# MCU_sheet.net
KiCad netlist of a schematic drawn in Altium Designer
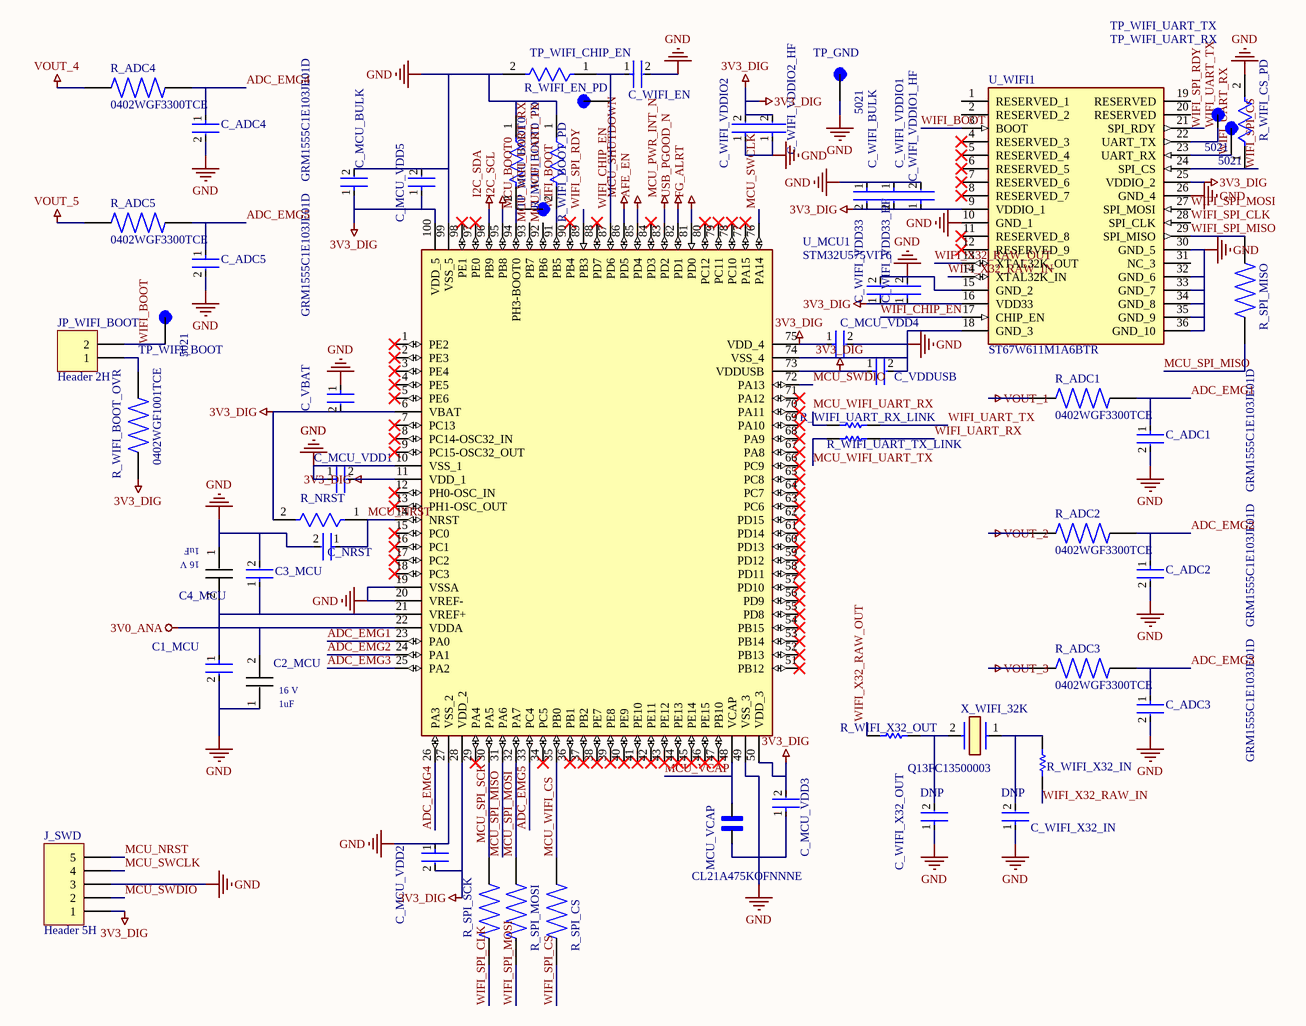
[diagram p0: MCU_sheet.SchDoc]

(export (version "E")
  (design (tool "Eeschema 10.0.6"))
  (components
    (comp (ref "C1_MCU")
      (value "GRM155R61C104KA88D")
      (footprint "96DF66F8-B997-472F-A885-42BCAAE661B2_FP-GRM155-0_05-IPC_C:FP-GRM155-0_05-IPC_C")
      (description "CAP CER 0.1UF 16V X5R 0402")
      (fields (field (name "VOLTAGE") "16V") (field (name "TOLERANCE") "10%"))
      (libsource (lib "EMG_Controlled_R5") (part "EMG_R5_C1_MCU"))
    )
    (comp (ref "C2_MCU")
      (value "MURATA_GRM155C71C105KE11D")
      (footprint "MURATA_GRM155C71C105KE11D_0:*MURATA_GRM155C71C105KE11D_0")
      (description "Murata GRM155C71C105KE11D: 1 uF 16 V X7S +/-10%, 0402/1005 metric")
      (fields (field (name "MF") "Murata") (field (name "MP") "GRM155C71C105KE11D"))
      (libsource (lib "EMG_Controlled_R5") (part "EMG_R5_C2_MCU"))
    )
    (comp (ref "C3_MCU")
      (value "GRM155R61C104KA88D")
      (footprint "96DF66F8-B997-472F-A885-42BCAAE661B2_FP-GRM155-0_05-IPC_C:FP-GRM155-0_05-IPC_C")
      (description "CAP CER 0.1UF 16V X5R 0402")
      (fields (field (name "VOLTAGE") "16V") (field (name "TOLERANCE") "10%"))
      (libsource (lib "EMG_Controlled_R5") (part "EMG_R5_C3_MCU"))
    )
    (comp (ref "C4_MCU")
      (value "MURATA_GRM155C71C105KE11D")
      (footprint "MURATA_GRM155C71C105KE11D_0:*MURATA_GRM155C71C105KE11D_0")
      (description "Murata GRM155C71C105KE11D: 1 uF 16 V X7S +/-10%, 0402/1005 metric")
      (fields (field (name "MF") "Murata") (field (name "MP") "GRM155C71C105KE11D"))
      (libsource (lib "EMG_Controlled_R5") (part "EMG_R5_C4_MCU"))
    )
    (comp (ref "C_ADC1")
      (value "GRM1555C1E103JE01D")
      (footprint "763A7EFC-D1AC-41FC-861F-90DBA274E34D_FP-GRM155-0_15-IPC_A:FP-GRM155-0_15-IPC_A")
      (description "Chip Multilayer Ceramic Capacitors for General Purpose, 0402, 10000pF, C0G, 30ppm/°C, 5%, 25V")
      (libsource (lib "EMG_Controlled_R5") (part "EMG_R5_C_ADC1"))
    )
    (comp (ref "C_ADC2")
      (value "GRM1555C1E103JE01D")
      (footprint "763A7EFC-D1AC-41FC-861F-90DBA274E34D_FP-GRM155-0_15-IPC_A:FP-GRM155-0_15-IPC_A")
      (description "Chip Multilayer Ceramic Capacitors for General Purpose, 0402, 10000pF, C0G, 30ppm/°C, 5%, 25V")
      (libsource (lib "EMG_Controlled_R5") (part "EMG_R5_C_ADC2"))
    )
    (comp (ref "C_ADC3")
      (value "GRM1555C1E103JE01D")
      (footprint "763A7EFC-D1AC-41FC-861F-90DBA274E34D_FP-GRM155-0_15-IPC_A:FP-GRM155-0_15-IPC_A")
      (description "Chip Multilayer Ceramic Capacitors for General Purpose, 0402, 10000pF, C0G, 30ppm/°C, 5%, 25V")
      (libsource (lib "EMG_Controlled_R5") (part "EMG_R5_C_ADC3"))
    )
    (comp (ref "C_ADC4")
      (value "GRM1555C1E103JE01D")
      (footprint "763A7EFC-D1AC-41FC-861F-90DBA274E34D_FP-GRM155-0_15-IPC_A:FP-GRM155-0_15-IPC_A")
      (description "Chip Multilayer Ceramic Capacitors for General Purpose, 0402, 10000pF, C0G, 30ppm/°C, 5%, 25V")
      (libsource (lib "EMG_Controlled_R5") (part "EMG_R5_C_ADC4"))
    )
    (comp (ref "C_ADC5")
      (value "GRM1555C1E103JE01D")
      (footprint "763A7EFC-D1AC-41FC-861F-90DBA274E34D_FP-GRM155-0_15-IPC_A:FP-GRM155-0_15-IPC_A")
      (description "Chip Multilayer Ceramic Capacitors for General Purpose, 0402, 10000pF, C0G, 30ppm/°C, 5%, 25V")
      (libsource (lib "EMG_Controlled_R5") (part "EMG_R5_C_ADC5"))
    )
    (comp (ref "C_MCU_BULK")
      (value "GCM21BC71E106KE36L")
      (footprint "936D640C-6583-4BC1-90EC-E059FB2B465D_FP-GCM21B-0_2-e0_2_0_7-MFG:FP-GCM21B-0_2-e0_2_0_7-MFG")
      (description "10 µF ±10% 25V Ceramic Capacitor X7S 0805 (2012 Metric)")
      (libsource (lib "EMG_Controlled_R5") (part "EMG_R5_C_MCU_BULK"))
    )
    (comp (ref "C_MCU_VDD1")
      (value "GRM155R61C104KA88D")
      (footprint "96DF66F8-B997-472F-A885-42BCAAE661B2_FP-GRM155-0_05-IPC_C:FP-GRM155-0_05-IPC_C")
      (description "CAP CER 0.1UF 16V X5R 0402")
      (fields (field (name "VOLTAGE") "16V") (field (name "TOLERANCE") "10%"))
      (libsource (lib "EMG_Controlled_R5") (part "EMG_R5_C_MCU_VDD1"))
    )
    (comp (ref "C_MCU_VDD2")
      (value "GRM155R61C104KA88D")
      (footprint "96DF66F8-B997-472F-A885-42BCAAE661B2_FP-GRM155-0_05-IPC_C:FP-GRM155-0_05-IPC_C")
      (description "CAP CER 0.1UF 16V X5R 0402")
      (fields (field (name "VOLTAGE") "16V") (field (name "TOLERANCE") "10%"))
      (libsource (lib "EMG_Controlled_R5") (part "EMG_R5_C_MCU_VDD2"))
    )
    (comp (ref "C_MCU_VDD3")
      (value "GRM155R61C104KA88D")
      (footprint "96DF66F8-B997-472F-A885-42BCAAE661B2_FP-GRM155-0_05-IPC_C:FP-GRM155-0_05-IPC_C")
      (description "CAP CER 0.1UF 16V X5R 0402")
      (fields (field (name "VOLTAGE") "16V") (field (name "TOLERANCE") "10%"))
      (libsource (lib "EMG_Controlled_R5") (part "EMG_R5_C_MCU_VDD3"))
    )
    (comp (ref "C_MCU_VDD4")
      (value "GRM155R61C104KA88D")
      (footprint "96DF66F8-B997-472F-A885-42BCAAE661B2_FP-GRM155-0_05-IPC_C:FP-GRM155-0_05-IPC_C")
      (description "CAP CER 0.1UF 16V X5R 0402")
      (fields (field (name "VOLTAGE") "16V") (field (name "TOLERANCE") "10%"))
      (libsource (lib "EMG_Controlled_R5") (part "EMG_R5_C_MCU_VDD4"))
    )
    (comp (ref "C_MCU_VDD5")
      (value "GRM155R61C104KA88D")
      (footprint "96DF66F8-B997-472F-A885-42BCAAE661B2_FP-GRM155-0_05-IPC_C:FP-GRM155-0_05-IPC_C")
      (description "CAP CER 0.1UF 16V X5R 0402")
      (fields (field (name "VOLTAGE") "16V") (field (name "TOLERANCE") "10%"))
      (libsource (lib "EMG_Controlled_R5") (part "EMG_R5_C_MCU_VDD5"))
    )
    (comp (ref "C_NRST")
      (value "GRM155R61C104KA88D")
      (footprint "96DF66F8-B997-472F-A885-42BCAAE661B2_FP-GRM155-0_05-IPC_C:FP-GRM155-0_05-IPC_C")
      (description "CAP CER 0.1UF 16V X5R 0402")
      (fields (field (name "VOLTAGE") "16V") (field (name "TOLERANCE") "10%"))
      (libsource (lib "EMG_Controlled_R5") (part "EMG_R5_C_NRST"))
    )
    (comp (ref "C_VBAT")
      (value "GRM155R61C104KA88D")
      (footprint "96DF66F8-B997-472F-A885-42BCAAE661B2_FP-GRM155-0_05-IPC_C:FP-GRM155-0_05-IPC_C")
      (description "CAP CER 0.1UF 16V X5R 0402")
      (fields (field (name "VOLTAGE") "16V") (field (name "TOLERANCE") "10%"))
      (libsource (lib "EMG_Controlled_R5") (part "EMG_R5_C_VBAT"))
    )
    (comp (ref "C_VDDUSB")
      (value "GRM155R61C104KA88D")
      (footprint "96DF66F8-B997-472F-A885-42BCAAE661B2_FP-GRM155-0_05-IPC_C:FP-GRM155-0_05-IPC_C")
      (description "CAP CER 0.1UF 16V X5R 0402")
      (fields (field (name "VOLTAGE") "16V") (field (name "TOLERANCE") "10%"))
      (libsource (lib "EMG_Controlled_R5") (part "EMG_R5_C_VDDUSB"))
    )
    (comp (ref "C_WIFI_BULK")
      (value "GRM219R60J476ME44D")
      (footprint "C53EA0CA-0507-449B-AA9E-0712004E71D5_FP-GRM219-0_2-0_1-IPC_A:FP-GRM219-0_2-0_1-IPC_A")
      (description "Chip Multilayer Ceramic Capacitors for General Purpose, 0805, 47uF, X5R, 15%, 20%, 6.3V")
      (fields (field (name "TOLERANCE") "20%"))
      (libsource (lib "EMG_Controlled_R5") (part "EMG_R5_C_WIFI_BULK"))
    )
    (comp (ref "C_WIFI_EN")
      (value "GRM155R61C104KA88D")
      (footprint "96DF66F8-B997-472F-A885-42BCAAE661B2_FP-GRM155-0_05-IPC_C:FP-GRM155-0_05-IPC_C")
      (description "CAP CER 0.1UF 16V X5R 0402")
      (fields (field (name "VOLTAGE") "16V") (field (name "TOLERANCE") "10%"))
      (libsource (lib "EMG_Controlled_R5") (part "EMG_R5_C_WIFI_EN"))
    )
    (comp (ref "C_WIFI_VDD33")
      (value "GCM21BC71E106KE36L")
      (footprint "936D640C-6583-4BC1-90EC-E059FB2B465D_FP-GCM21B-0_2-e0_2_0_7-MFG:FP-GCM21B-0_2-e0_2_0_7-MFG")
      (description "10 µF ±10% 25V Ceramic Capacitor X7S 0805 (2012 Metric)")
      (libsource (lib "EMG_Controlled_R5") (part "EMG_R5_C_WIFI_VDD33"))
    )
    (comp (ref "C_WIFI_VDD33_HF")
      (value "GRM155R61C104KA88D")
      (footprint "DB04E9CC-B2FF-43A3-BDC5-6EF387B10263_FP-GRM155-0_05-MFG:FP-GRM155-0_05-MFG")
      (description "CAP CER 0.1UF 16V X5R 0402")
      (fields (field (name "VOLTAGE") "16V") (field (name "TOLERANCE") "10%"))
      (libsource (lib "EMG_Controlled_R5") (part "EMG_R5_C_WIFI_VDD33_HF"))
    )
    (comp (ref "C_WIFI_VDDIO1")
      (value "GCM21BC71E106KE36L")
      (footprint "936D640C-6583-4BC1-90EC-E059FB2B465D_FP-GCM21B-0_2-e0_2_0_7-MFG:FP-GCM21B-0_2-e0_2_0_7-MFG")
      (description "10 µF ±10% 25V Ceramic Capacitor X7S 0805 (2012 Metric)")
      (libsource (lib "EMG_Controlled_R5") (part "EMG_R5_C_WIFI_VDDIO1"))
    )
    (comp (ref "C_WIFI_VDDIO1_HF")
      (value "GRM155R61C104KA88D")
      (footprint "DB04E9CC-B2FF-43A3-BDC5-6EF387B10263_FP-GRM155-0_05-MFG:FP-GRM155-0_05-MFG")
      (description "CAP CER 0.1UF 16V X5R 0402")
      (fields (field (name "VOLTAGE") "16V") (field (name "TOLERANCE") "10%"))
      (libsource (lib "EMG_Controlled_R5") (part "EMG_R5_C_WIFI_VDDIO1_HF"))
    )
    (comp (ref "C_WIFI_VDDIO2")
      (value "GCM21BC71E106KE36L")
      (footprint "936D640C-6583-4BC1-90EC-E059FB2B465D_FP-GCM21B-0_2-e0_2_0_7-MFG:FP-GCM21B-0_2-e0_2_0_7-MFG")
      (description "10 µF ±10% 25V Ceramic Capacitor X7S 0805 (2012 Metric)")
      (libsource (lib "EMG_Controlled_R5") (part "EMG_R5_C_WIFI_VDDIO2"))
    )
    (comp (ref "C_WIFI_VDDIO2_HF")
      (value "GRM155R61C104KA88D")
      (footprint "DB04E9CC-B2FF-43A3-BDC5-6EF387B10263_FP-GRM155-0_05-MFG:FP-GRM155-0_05-MFG")
      (description "CAP CER 0.1UF 16V X5R 0402")
      (fields (field (name "VOLTAGE") "16V") (field (name "TOLERANCE") "10%"))
      (libsource (lib "EMG_Controlled_R5") (part "EMG_R5_C_WIFI_VDDIO2_HF"))
    )
    (comp (ref "C_WIFI_X32_IN")
      (value "DNP")
      (footprint "96DF66F8-B997-472F-A885-42BCAAE661B2_FP-GRM155-0_05-IPC_C:FP-GRM155-0_05-IPC_C")
      (description "DNP - 32 kHz crystal tuning capacitor; no fitted value or MPN; retain 0402 footprint")
      (libsource (lib "EMG_Controlled_R5") (part "EMG_R5_C_WIFI_X32_IN"))
    )
    (comp (ref "C_WIFI_X32_OUT")
      (value "DNP")
      (footprint "96DF66F8-B997-472F-A885-42BCAAE661B2_FP-GRM155-0_05-IPC_C:FP-GRM155-0_05-IPC_C")
      (description "DNP - 32 kHz crystal tuning capacitor; no fitted value or MPN; retain 0402 footprint")
      (libsource (lib "EMG_Controlled_R5") (part "EMG_R5_C_WIFI_X32_OUT"))
    )
    (comp (ref "JP_WIFI_BOOT")
      (value "Header 2H")
      (footprint "EMG_Service_C2B:EMG_SJ_2P_NO")
      (description "Header, 2-Pin, Right Angle")
      (fields (field (name "PUBLISHER") "Altium Limited"))
      (libsource (lib "EMG_Controlled_R5") (part "EMG_R5_JP_WIFI_BOOT"))
    )
    (comp (ref "J_SWD")
      (value "Header 5H")
      (footprint "EMG_Service_C2B:EMG_TC2030_NL")
      (description "Header, 5-Pin, Right Angle")
      (fields (field (name "PUBLISHER") "Altium Limited"))
      (libsource (lib "EMG_Controlled_R5") (part "EMG_R5_J_SWD"))
    )
    (comp (ref "MCU_VCAP")
      (value "CL21A475KOFNNNE")
      (footprint "CL21A475KOFNNNE_0:CAPC2012X135N")
      (description "4.7 ÂµF Â±10% 16V Ceramic Capacitor X5R 0805 (2012 Metric)")
      (fields (field (name "MF") "Samsung"))
      (libsource (lib "EMG_Controlled_R5") (part "EMG_R5_MCU_VCAP"))
    )
    (comp (ref "R_ADC1")
      (value "0402WGF3300TCE")
      (footprint "0402WGF3300TCE_0:RESC1005X40N")
      (description "330 Ohm 1/16W Thick Film Resistor 0402 Chip - Surface Mount")
      (fields (field (name "MF") "Uni-Royal"))
      (libsource (lib "EMG_Controlled_R5") (part "EMG_R5_R_ADC1"))
    )
    (comp (ref "R_ADC2")
      (value "0402WGF3300TCE")
      (footprint "0402WGF3300TCE_0:RESC1005X40N")
      (description "330 Ohm 1/16W Thick Film Resistor 0402 Chip - Surface Mount")
      (fields (field (name "MF") "Uni-Royal"))
      (libsource (lib "EMG_Controlled_R5") (part "EMG_R5_R_ADC2"))
    )
    (comp (ref "R_ADC3")
      (value "0402WGF3300TCE")
      (footprint "0402WGF3300TCE_0:RESC1005X40N")
      (description "330 Ohm 1/16W Thick Film Resistor 0402 Chip - Surface Mount")
      (fields (field (name "MF") "Uni-Royal"))
      (libsource (lib "EMG_Controlled_R5") (part "EMG_R5_R_ADC3"))
    )
    (comp (ref "R_ADC4")
      (value "0402WGF3300TCE")
      (footprint "0402WGF3300TCE_0:RESC1005X40N")
      (description "330 Ohm 1/16W Thick Film Resistor 0402 Chip - Surface Mount")
      (fields (field (name "MF") "Uni-Royal"))
      (libsource (lib "EMG_Controlled_R5") (part "EMG_R5_R_ADC4"))
    )
    (comp (ref "R_ADC5")
      (value "0402WGF3300TCE")
      (footprint "0402WGF3300TCE_0:RESC1005X40N")
      (description "330 Ohm 1/16W Thick Film Resistor 0402 Chip - Surface Mount")
      (fields (field (name "MF") "Uni-Royal"))
      (libsource (lib "EMG_Controlled_R5") (part "EMG_R5_R_ADC5"))
    )
    (comp (ref "R_MCU_BOOT0_PD")
      (value "RT0402BRD0710KL")
      (footprint "B876F212-A29A-4983-9BB8-539D1BA2EBA1_FP-RT0402-MFG:FP-RT0402-MFG")
      (description "RES 10.0K OHM 1/16W .1% SMD 0402")
      (fields
        (field (name "MANUFACTURER") "Yageo")
        (field (name "OCTOPART") "https://octopart.com/rt0402brd0710kl-yageo-1181432")
      )
      (libsource (lib "EMG_Controlled_R5") (part "EMG_R5_R_MCU_BOOT0_PD"))
    )
    (comp (ref "R_NRST")
      (value "RT0402BRD0710KL")
      (footprint "B876F212-A29A-4983-9BB8-539D1BA2EBA1_FP-RT0402-MFG:FP-RT0402-MFG")
      (description "RES 10.0K OHM 1/16W .1% SMD 0402")
      (fields
        (field (name "MANUFACTURER") "Yageo")
        (field (name "OCTOPART") "https://octopart.com/rt0402brd0710kl-yageo-1181432")
      )
      (libsource (lib "EMG_Controlled_R5") (part "EMG_R5_R_NRST"))
    )
    (comp (ref "R_SPI_CS")
      (value "ERJ2RKF22R0X")
      (footprint "ERJ2RKF22R0X_0:RES_ERJ2RKF22R0X")
      (description "22 Ohms Â±1% 0.1W, 1/10W Chip Resistor 0402 (1005 Metric) Automotive AEC-Q200 Thick Film")
      (fields (field (name "MF") "Panasonic") (field (name "DIGI-KEY_PART_NUMBER") "P22.0LTR-ND"))
      (libsource (lib "EMG_Controlled_R5") (part "EMG_R5_R_SPI_CS"))
    )
    (comp (ref "R_SPI_MISO")
      (value "ERJ2RKF22R0X")
      (footprint "ERJ2RKF22R0X_0:RES_ERJ2RKF22R0X")
      (description "22 Ohms Â±1% 0.1W, 1/10W Chip Resistor 0402 (1005 Metric) Automotive AEC-Q200 Thick Film")
      (fields (field (name "MF") "Panasonic") (field (name "DIGI-KEY_PART_NUMBER") "P22.0LTR-ND"))
      (libsource (lib "EMG_Controlled_R5") (part "EMG_R5_R_SPI_MISO"))
    )
    (comp (ref "R_SPI_MOSI")
      (value "ERJ2RKF22R0X")
      (footprint "ERJ2RKF22R0X_0:RES_ERJ2RKF22R0X")
      (description "22 Ohms Â±1% 0.1W, 1/10W Chip Resistor 0402 (1005 Metric) Automotive AEC-Q200 Thick Film")
      (fields (field (name "MF") "Panasonic") (field (name "DIGI-KEY_PART_NUMBER") "P22.0LTR-ND"))
      (libsource (lib "EMG_Controlled_R5") (part "EMG_R5_R_SPI_MOSI"))
    )
    (comp (ref "R_SPI_SCK")
      (value "ERJ2RKF22R0X")
      (footprint "ERJ2RKF22R0X_0:RES_ERJ2RKF22R0X")
      (description "22 Ohms Â±1% 0.1W, 1/10W Chip Resistor 0402 (1005 Metric) Automotive AEC-Q200 Thick Film")
      (fields (field (name "MF") "Panasonic") (field (name "DIGI-KEY_PART_NUMBER") "P22.0LTR-ND"))
      (libsource (lib "EMG_Controlled_R5") (part "EMG_R5_R_SPI_SCK"))
    )
    (comp (ref "R_WIFI_BOOT_OVR")
      (value "0402WGF1001TCE")
      (footprint "0402WGF1001TCE_0:RESC1005X40N")
      (description "1K Ohm 1/16W Thick Film Resistor 0402 Chip - Surface Mount")
      (fields (field (name "MF") "Uni-Royal"))
      (libsource (lib "EMG_Controlled_R5") (part "EMG_R5_R_WIFI_BOOT_OVR"))
    )
    (comp (ref "R_WIFI_BOOT_PD")
      (value "RT0402BRD0710KL")
      (footprint "B876F212-A29A-4983-9BB8-539D1BA2EBA1_FP-RT0402-MFG:FP-RT0402-MFG")
      (description "RES 10.0K OHM 1/16W .1% SMD 0402")
      (fields
        (field (name "MANUFACTURER") "Yageo")
        (field (name "OCTOPART") "https://octopart.com/rt0402brd0710kl-yageo-1181432")
      )
      (libsource (lib "EMG_Controlled_R5") (part "EMG_R5_R_WIFI_BOOT_PD"))
    )
    (comp (ref "R_WIFI_CS_PD")
      (value "RT0402BRD0710KL")
      (footprint "B876F212-A29A-4983-9BB8-539D1BA2EBA1_FP-RT0402-MFG:FP-RT0402-MFG")
      (description "RES 10.0K OHM 1/16W .1% SMD 0402")
      (fields
        (field (name "MANUFACTURER") "Yageo")
        (field (name "OCTOPART") "https://octopart.com/rt0402brd0710kl-yageo-1181432")
      )
      (libsource (lib "EMG_Controlled_R5") (part "EMG_R5_R_WIFI_CS_PD"))
    )
    (comp (ref "R_WIFI_EN_PD")
      (value "RT0402BRD0710KL")
      (footprint "B876F212-A29A-4983-9BB8-539D1BA2EBA1_FP-RT0402-MFG:FP-RT0402-MFG")
      (description "RES 10.0K OHM 1/16W .1% SMD 0402")
      (fields
        (field (name "MANUFACTURER") "Yageo")
        (field (name "OCTOPART") "https://octopart.com/rt0402brd0710kl-yageo-1181432")
      )
      (libsource (lib "EMG_Controlled_R5") (part "EMG_R5_R_WIFI_EN_PD"))
    )
    (comp (ref "R_WIFI_UART_RX_LINK")
      (value "ERJ2GE0R00X")
      (footprint "9A3BC7AA-5BFE-4103-83F7-76F281EFC21D_RESC1005X40X25LL05T05:RESC1005X40X25LL05T05")
      (description "Chip Resistor, 0 Ohm, 0.1 W, -55 to 155 degC, 0402 (1005 Metric), RoHS, Tape and Reel")
      (fields (field (name "MANUFACTURER") "Panasonic") (field (name "TOLERANCE") "5%"))
      (libsource (lib "EMG_Controlled_R5") (part "EMG_R5_R_WIFI_UART_RX_LINK"))
    )
    (comp (ref "R_WIFI_UART_TX_LINK")
      (value "ERJ2GE0R00X")
      (footprint "9A3BC7AA-5BFE-4103-83F7-76F281EFC21D_RESC1005X40X25LL05T05:RESC1005X40X25LL05T05")
      (description "Chip Resistor, 0 Ohm, 0.1 W, -55 to 155 degC, 0402 (1005 Metric), RoHS, Tape and Reel")
      (fields (field (name "MANUFACTURER") "Panasonic") (field (name "TOLERANCE") "5%"))
      (libsource (lib "EMG_Controlled_R5") (part "EMG_R5_R_WIFI_UART_TX_LINK"))
    )
    (comp (ref "R_WIFI_X32_IN")
      (value "ERJ2GE0R00X")
      (footprint "9A3BC7AA-5BFE-4103-83F7-76F281EFC21D_RESC1005X40X25LL05T05:RESC1005X40X25LL05T05")
      (description "Chip Resistor, 0 Ohm, 0.1 W, -55 to 155 degC, 0402 (1005 Metric), RoHS, Tape and Reel")
      (fields (field (name "MANUFACTURER") "Panasonic") (field (name "TOLERANCE") "5%"))
      (libsource (lib "EMG_Controlled_R5") (part "EMG_R5_R_WIFI_X32_IN"))
    )
    (comp (ref "R_WIFI_X32_OUT")
      (value "ERJ2GE0R00X")
      (footprint "9A3BC7AA-5BFE-4103-83F7-76F281EFC21D_RESC1005X40X25LL05T05:RESC1005X40X25LL05T05")
      (description "Chip Resistor, 0 Ohm, 0.1 W, -55 to 155 degC, 0402 (1005 Metric), RoHS, Tape and Reel")
      (fields (field (name "MANUFACTURER") "Panasonic") (field (name "TOLERANCE") "5%"))
      (libsource (lib "EMG_Controlled_R5") (part "EMG_R5_R_WIFI_X32_OUT"))
    )
    (comp (ref "TP_GND")
      (value "5021")
      (footprint "EMG_Service_C2B:EMG_TP_FLAT_1R2")
      (description "UltraLow Profile THM Test Point-No Base")
      (fields (field (name "MF") "Keystone Electronics"))
      (libsource (lib "EMG_Controlled_R5") (part "EMG_R5_TP_GND"))
    )
    (comp (ref "TP_MCU_BOOT0")
      (value "5021")
      (footprint "EMG_Service_C2B:EMG_TP_FLAT_1R2")
      (description "UltraLow Profile THM Test Point-No Base")
      (fields (field (name "MF") "Keystone Electronics"))
      (libsource (lib "EMG_Controlled_R5") (part "EMG_R5_TP_MCU_BOOT0"))
    )
    (comp (ref "TP_WIFI_BOOT")
      (value "5021")
      (footprint "EMG_Service_C2B:EMG_TP_FLAT_1R2")
      (description "UltraLow Profile THM Test Point-No Base")
      (fields (field (name "MF") "Keystone Electronics"))
      (libsource (lib "EMG_Controlled_R5") (part "EMG_R5_TP_WIFI_BOOT"))
    )
    (comp (ref "TP_WIFI_CHIP_EN")
      (value "5021")
      (footprint "EMG_Service_C2B:EMG_TP_FLAT_1R2")
      (description "UltraLow Profile THM Test Point-No Base")
      (fields (field (name "MF") "Keystone Electronics"))
      (libsource (lib "EMG_Controlled_R5") (part "EMG_R5_TP_WIFI_CHIP_EN"))
    )
    (comp (ref "TP_WIFI_UART_RX")
      (value "5021")
      (footprint "EMG_Service_C2B:EMG_TP_FLAT_1R2")
      (description "UltraLow Profile THM Test Point-No Base")
      (fields (field (name "MF") "Keystone Electronics"))
      (libsource (lib "EMG_Controlled_R5") (part "EMG_R5_TP_WIFI_UART_RX"))
    )
    (comp (ref "TP_WIFI_UART_TX")
      (value "5021")
      (footprint "EMG_Service_C2B:EMG_TP_FLAT_1R2")
      (description "UltraLow Profile THM Test Point-No Base")
      (fields (field (name "MF") "Keystone Electronics"))
      (libsource (lib "EMG_Controlled_R5") (part "EMG_R5_TP_WIFI_UART_TX"))
    )
    (comp (ref "U_MCU1")
      (value "STM32U575VIT6")
      (footprint "SamacSys:QFP50P1600X1600X160-100N")
      (description "Integrated Circuit")
      (fields (field (name "MOUSER PART NUMBER") "511-STM32U575VIT6"))
      (libsource (lib "EMG_Controlled_R5") (part "EMG_R5_U_MCU1"))
    )
    (comp (ref "U_WIFI1")
      (value "ST67W611M1A6BTR")
      (footprint "SamacSys:ST67W611M1A6BTR")
      (description "Integrated Circuit")
      (libsource (lib "EMG_Controlled_R5") (part "EMG_R5_U_WIFI1"))
    )
    (comp (ref "X_WIFI_32K")
      (value "Q13FC13500003")
      (footprint "EMG_Crystal_R5:EMG_FC135_3215_2P")
      (description "Epson FC-135 32.768 kHz 9 pF +/-20 ppm, ESR 70 kohm max, 3.2x1.5 mm, 2 terminals")
      (fields
        (field (name "MANUFACTURER") "Seiko Epson Corporation")
        (field (name "TOLERANCE") "+/-20 ppm at 25 degC, 0.1 uW")
      )
      (libsource (lib "EMG_Controlled_R5") (part "EMG_R5_X_WIFI_32K"))
    )
  )
  (nets
    (net (code "1") (name "/ADC_EMG1") (class "Default")
      (node (ref "C_ADC1") (pin "1") (pinfunction "1_1") (pintype "passive"))
      (node (ref "R_ADC1") (pin "2") (pinfunction "2_2") (pintype "passive"))
      (node (ref "U_MCU1") (pin "23") (pinfunction "PA0_23") (pintype "bidirectional"))
    )
    (net (code "2") (name "/ADC_EMG2") (class "Default")
      (node (ref "C_ADC2") (pin "1") (pinfunction "1_1") (pintype "passive"))
      (node (ref "R_ADC2") (pin "2") (pinfunction "2_2") (pintype "passive"))
      (node (ref "U_MCU1") (pin "24") (pinfunction "PA1_24") (pintype "bidirectional"))
    )
    (net (code "3") (name "/ADC_EMG3") (class "Default")
      (node (ref "C_ADC3") (pin "1") (pinfunction "1_1") (pintype "passive"))
      (node (ref "R_ADC3") (pin "2") (pinfunction "2_2") (pintype "passive"))
      (node (ref "U_MCU1") (pin "25") (pinfunction "PA2_25") (pintype "bidirectional"))
    )
    (net (code "4") (name "/ADC_EMG4") (class "Default")
      (node (ref "C_ADC4") (pin "1") (pinfunction "1_1") (pintype "passive"))
      (node (ref "R_ADC4") (pin "2") (pinfunction "2_2") (pintype "passive"))
      (node (ref "U_MCU1") (pin "26") (pinfunction "PA3_26") (pintype "bidirectional"))
    )
    (net (code "5") (name "/ADC_EMG5") (class "Default")
      (node (ref "C_ADC5") (pin "1") (pinfunction "1_1") (pintype "passive"))
      (node (ref "R_ADC5") (pin "2") (pinfunction "2_2") (pintype "passive"))
      (node (ref "U_MCU1") (pin "33") (pinfunction "PC4_33") (pintype "bidirectional"))
    )
    (net (code "6") (name "/MCU_BOOT0") (class "Default")
      (node (ref "R_MCU_BOOT0_PD") (pin "2") (pinfunction "2_2") (pintype "passive"))
      (node (ref "TP_MCU_BOOT0") (pin "TP") (pinfunction "TP_TP") (pintype "passive"))
      (node (ref "U_MCU1") (pin "94") (pinfunction "PH3-BOOT0_94") (pintype "bidirectional"))
    )
    (net (code "7") (name "/MCU_NRST") (class "Default")
      (node (ref "C_NRST") (pin "1") (pinfunction "1_1") (pintype "passive"))
      (node (ref "J_SWD") (pin "5") (pinfunction "5_5") (pintype "passive"))
      (node (ref "R_NRST") (pin "1") (pinfunction "1_1") (pintype "passive"))
      (node (ref "U_MCU1") (pin "14") (pinfunction "NRST_14") (pintype "bidirectional"))
    )
    (net (code "8") (name "/MCU_SPI_MISO") (class "Default")
      (node (ref "R_SPI_MISO") (pin "2") (pinfunction "2_2") (pintype "passive"))
      (node (ref "U_MCU1") (pin "31") (pinfunction "PA6_31") (pintype "bidirectional"))
    )
    (net (code "9") (name "/MCU_SPI_MOSI") (class "Default")
      (node (ref "R_SPI_MOSI") (pin "2") (pinfunction "2_2") (pintype "passive"))
      (node (ref "U_MCU1") (pin "32") (pinfunction "PA7_32") (pintype "bidirectional"))
    )
    (net (code "10") (name "/MCU_SPI_SCK") (class "Default")
      (node (ref "R_SPI_SCK") (pin "2") (pinfunction "2_2") (pintype "passive"))
      (node (ref "U_MCU1") (pin "30") (pinfunction "PA5_30") (pintype "bidirectional"))
    )
    (net (code "11") (name "/MCU_SWCLK") (class "Default")
      (node (ref "J_SWD") (pin "4") (pinfunction "4_4") (pintype "passive"))
      (node (ref "U_MCU1") (pin "76") (pinfunction "PA14_76") (pintype "bidirectional"))
    )
    (net (code "12") (name "/MCU_SWDIO") (class "Default")
      (node (ref "J_SWD") (pin "2") (pinfunction "2_2") (pintype "passive"))
      (node (ref "U_MCU1") (pin "72") (pinfunction "PA13_72") (pintype "bidirectional"))
    )
    (net (code "13") (name "/MCU_VCAP") (class "Default")
      (node (ref "MCU_VCAP") (pin "2") (pinfunction "2_2") (pintype "passive"))
      (node (ref "U_MCU1") (pin "48") (pinfunction "VCAP_48") (pintype "power_in"))
    )
    (net (code "14") (name "/MCU_WIFI_CS") (class "Default")
      (node (ref "R_SPI_CS") (pin "2") (pinfunction "2_2") (pintype "passive"))
      (node (ref "U_MCU1") (pin "35") (pinfunction "PB0_35") (pintype "bidirectional"))
    )
    (net (code "15") (name "/MCU_WIFI_UART_RX") (class "Default")
      (node (ref "R_WIFI_UART_RX_LINK") (pin "2") (pinfunction "2_2") (pintype "passive"))
      (node (ref "U_MCU1") (pin "93") (pinfunction "PB7_93") (pintype "bidirectional"))
    )
    (net (code "16") (name "/MCU_WIFI_UART_TX") (class "Default")
      (node (ref "R_WIFI_UART_TX_LINK") (pin "2") (pinfunction "2_2") (pintype "passive"))
      (node (ref "U_MCU1") (pin "92") (pinfunction "PB6_92") (pintype "bidirectional"))
    )
    (net (code "17") (name "/WIFI_BOOT") (class "Default")
      (node (ref "JP_WIFI_BOOT") (pin "2") (pinfunction "2_2") (pintype "passive"))
      (node (ref "R_WIFI_BOOT_PD") (pin "2") (pinfunction "2_2") (pintype "passive"))
      (node (ref "TP_WIFI_BOOT") (pin "TP") (pinfunction "TP_TP") (pintype "passive"))
      (node (ref "U_MCU1") (pin "91") (pinfunction "PB5_91") (pintype "bidirectional"))
      (node (ref "U_WIFI1") (pin "3") (pinfunction "BOOT_3") (pintype "input"))
    )
    (net (code "18") (name "/WIFI_CHIP_EN") (class "Default")
      (node (ref "C_WIFI_EN") (pin "1") (pinfunction "1_1") (pintype "passive"))
      (node (ref "R_WIFI_EN_PD") (pin "1") (pinfunction "1_1") (pintype "passive"))
      (node (ref "TP_WIFI_CHIP_EN") (pin "TP") (pinfunction "TP_TP") (pintype "passive"))
      (node (ref "U_MCU1") (pin "87") (pinfunction "PD6_87") (pintype "bidirectional"))
      (node (ref "U_WIFI1") (pin "17") (pinfunction "CHIP_EN_17") (pintype "input"))
    )
    (net (code "19") (name "/WIFI_SPI_CLK") (class "Default")
      (node (ref "R_SPI_SCK") (pin "1") (pinfunction "1_1") (pintype "passive"))
      (node (ref "U_WIFI1") (pin "28") (pinfunction "SPI_CLK_28") (pintype "input"))
    )
    (net (code "20") (name "/WIFI_SPI_CS") (class "Default")
      (node (ref "R_SPI_CS") (pin "1") (pinfunction "1_1") (pintype "passive"))
      (node (ref "R_WIFI_CS_PD") (pin "1") (pinfunction "1_1") (pintype "passive"))
      (node (ref "U_WIFI1") (pin "24") (pinfunction "SPI_CS_24") (pintype "input"))
    )
    (net (code "21") (name "/WIFI_SPI_MISO") (class "Default")
      (node (ref "R_SPI_MISO") (pin "1") (pinfunction "1_1") (pintype "passive"))
      (node (ref "U_WIFI1") (pin "29") (pinfunction "SPI_MISO_29") (pintype "output"))
    )
    (net (code "22") (name "/WIFI_SPI_MOSI") (class "Default")
      (node (ref "R_SPI_MOSI") (pin "1") (pinfunction "1_1") (pintype "passive"))
      (node (ref "U_WIFI1") (pin "27") (pinfunction "SPI_MOSI_27") (pintype "input"))
    )
    (net (code "23") (name "/WIFI_SPI_RDY") (class "Default")
      (node (ref "U_MCU1") (pin "89") (pinfunction "PB3_89") (pintype "input"))
      (node (ref "U_WIFI1") (pin "21") (pinfunction "SPI_RDY_21") (pintype "output"))
    )
    (net (code "24") (name "/WIFI_UART_RX") (class "Default")
      (node (ref "R_WIFI_UART_TX_LINK") (pin "1") (pinfunction "1_1") (pintype "passive"))
      (node (ref "TP_WIFI_UART_RX") (pin "TP") (pinfunction "TP_TP") (pintype "passive"))
      (node (ref "U_WIFI1") (pin "23") (pinfunction "UART_RX_23") (pintype "input"))
    )
    (net (code "25") (name "/WIFI_UART_TX") (class "Default")
      (node (ref "R_WIFI_UART_RX_LINK") (pin "1") (pinfunction "1_1") (pintype "passive"))
      (node (ref "TP_WIFI_UART_TX") (pin "TP") (pinfunction "TP_TP") (pintype "passive"))
      (node (ref "U_WIFI1") (pin "22") (pinfunction "UART_TX_22") (pintype "output"))
    )
    (net (code "26") (name "/WIFI_X32_RAW_IN") (class "Default")
      (node (ref "R_WIFI_X32_IN") (pin "2") (pinfunction "2_2") (pintype "passive"))
      (node (ref "U_WIFI1") (pin "14") (pinfunction "XTAL32K_IN_14") (pintype "bidirectional"))
    )
    (net (code "27") (name "/WIFI_X32_RAW_OUT") (class "Default")
      (node (ref "R_WIFI_X32_OUT") (pin "2") (pinfunction "2_2") (pintype "passive"))
      (node (ref "U_WIFI1") (pin "13") (pinfunction "XTAL32K_OUT_13") (pintype "bidirectional"))
    )
    (net (code "28") (name "3V0_ANA") (class "Default")
      (node (ref "C1_MCU") (pin "1") (pinfunction "1_1") (pintype "passive"))
      (node (ref "C2_MCU") (pin "2") (pinfunction "2_2") (pintype "passive"))
      (node (ref "C3_MCU") (pin "1") (pinfunction "1_1") (pintype "passive"))
      (node (ref "C4_MCU") (pin "2") (pinfunction "2_2") (pintype "passive"))
      (node (ref "U_MCU1") (pin "21") (pinfunction "VREF+_21") (pintype "power_in"))
      (node (ref "U_MCU1") (pin "22") (pinfunction "VDDA_22") (pintype "power_in"))
    )
    (net (code "29") (name "3V3_DIG") (class "Default")
      (node (ref "C_MCU_BULK") (pin "1") (pinfunction "1_1") (pintype "passive"))
      (node (ref "C_MCU_VDD1") (pin "2") (pinfunction "2_2") (pintype "passive"))
      (node (ref "C_MCU_VDD2") (pin "2") (pinfunction "2_2") (pintype "passive"))
      (node (ref "C_MCU_VDD3") (pin "2") (pinfunction "2_2") (pintype "passive"))
      (node (ref "C_MCU_VDD4") (pin "1") (pinfunction "1_1") (pintype "passive"))
      (node (ref "C_MCU_VDD5") (pin "1") (pinfunction "1_1") (pintype "passive"))
      (node (ref "C_VBAT") (pin "2") (pinfunction "2_2") (pintype "passive"))
      (node (ref "C_VDDUSB") (pin "1") (pinfunction "1_1") (pintype "passive"))
      (node (ref "C_WIFI_BULK") (pin "2") (pinfunction "2_2") (pintype "passive"))
      (node (ref "C_WIFI_VDD33") (pin "1") (pinfunction "1_1") (pintype "passive"))
      (node (ref "C_WIFI_VDD33_HF") (pin "1") (pinfunction "1_1") (pintype "passive"))
      (node (ref "C_WIFI_VDDIO1") (pin "2") (pinfunction "2_2") (pintype "passive"))
      (node (ref "C_WIFI_VDDIO1_HF") (pin "1") (pinfunction "1_1") (pintype "passive"))
      (node (ref "C_WIFI_VDDIO2") (pin "2") (pinfunction "2_2") (pintype "passive"))
      (node (ref "C_WIFI_VDDIO2_HF") (pin "2") (pinfunction "2_2") (pintype "passive"))
      (node (ref "J_SWD") (pin "1") (pinfunction "1_1") (pintype "passive"))
      (node (ref "R_NRST") (pin "2") (pinfunction "2_2") (pintype "passive"))
      (node (ref "R_WIFI_BOOT_OVR") (pin "1") (pinfunction "1_1") (pintype "passive"))
      (node (ref "U_MCU1") (pin "100") (pinfunction "VDD_5_100") (pintype "power_in"))
      (node (ref "U_MCU1") (pin "11") (pinfunction "VDD_1_11") (pintype "power_in"))
      (node (ref "U_MCU1") (pin "28") (pinfunction "VDD_2_28") (pintype "power_in"))
      (node (ref "U_MCU1") (pin "50") (pinfunction "VDD_3_50") (pintype "power_in"))
      (node (ref "U_MCU1") (pin "6") (pinfunction "VBAT_6") (pintype "power_in"))
      (node (ref "U_MCU1") (pin "73") (pinfunction "VDDUSB_73") (pintype "power_in"))
      (node (ref "U_MCU1") (pin "75") (pinfunction "VDD_4_75") (pintype "power_in"))
      (node (ref "U_WIFI1") (pin "16") (pinfunction "VDD33_16") (pintype "power_in"))
      (node (ref "U_WIFI1") (pin "25") (pinfunction "VDDIO_2_25") (pintype "power_in"))
      (node (ref "U_WIFI1") (pin "9") (pinfunction "VDDIO_1_9") (pintype "power_in"))
    )
    (net (code "30") (name "AFE_EN") (class "Default")
      (node (ref "U_MCU1") (pin "85") (pinfunction "PD4_85") (pintype "bidirectional"))
    )
    (net (code "31") (name "FG_ALRT") (class "Default")
      (node (ref "U_MCU1") (pin "81") (pinfunction "PD0_81") (pintype "input"))
    )
    (net (code "32") (name "GND") (class "Default")
      (node (ref "C1_MCU") (pin "2") (pinfunction "2_2") (pintype "passive"))
      (node (ref "C2_MCU") (pin "1") (pinfunction "1_1") (pintype "passive"))
      (node (ref "C3_MCU") (pin "2") (pinfunction "2_2") (pintype "passive"))
      (node (ref "C4_MCU") (pin "1") (pinfunction "1_1") (pintype "passive"))
      (node (ref "C_ADC1") (pin "2") (pinfunction "2_2") (pintype "passive"))
      (node (ref "C_ADC2") (pin "2") (pinfunction "2_2") (pintype "passive"))
      (node (ref "C_ADC3") (pin "2") (pinfunction "2_2") (pintype "passive"))
      (node (ref "C_ADC4") (pin "2") (pinfunction "2_2") (pintype "passive"))
      (node (ref "C_ADC5") (pin "2") (pinfunction "2_2") (pintype "passive"))
      (node (ref "C_MCU_BULK") (pin "2") (pinfunction "2_2") (pintype "passive"))
      (node (ref "C_MCU_VDD1") (pin "1") (pinfunction "1_1") (pintype "passive"))
      (node (ref "C_MCU_VDD2") (pin "1") (pinfunction "1_1") (pintype "passive"))
      (node (ref "C_MCU_VDD3") (pin "1") (pinfunction "1_1") (pintype "passive"))
      (node (ref "C_MCU_VDD4") (pin "2") (pinfunction "2_2") (pintype "passive"))
      (node (ref "C_MCU_VDD5") (pin "2") (pinfunction "2_2") (pintype "passive"))
      (node (ref "C_NRST") (pin "2") (pinfunction "2_2") (pintype "passive"))
      (node (ref "C_VBAT") (pin "1") (pinfunction "1_1") (pintype "passive"))
      (node (ref "C_VDDUSB") (pin "2") (pinfunction "2_2") (pintype "passive"))
      (node (ref "C_WIFI_BULK") (pin "1") (pinfunction "1_1") (pintype "passive"))
      (node (ref "C_WIFI_EN") (pin "2") (pinfunction "2_2") (pintype "passive"))
      (node (ref "C_WIFI_VDD33") (pin "2") (pinfunction "2_2") (pintype "passive"))
      (node (ref "C_WIFI_VDD33_HF") (pin "2") (pinfunction "2_2") (pintype "passive"))
      (node (ref "C_WIFI_VDDIO1") (pin "1") (pinfunction "1_1") (pintype "passive"))
      (node (ref "C_WIFI_VDDIO1_HF") (pin "2") (pinfunction "2_2") (pintype "passive"))
      (node (ref "C_WIFI_VDDIO2") (pin "1") (pinfunction "1_1") (pintype "passive"))
      (node (ref "C_WIFI_VDDIO2_HF") (pin "1") (pinfunction "1_1") (pintype "passive"))
      (node (ref "C_WIFI_X32_IN") (pin "1") (pinfunction "1_1") (pintype "passive"))
      (node (ref "C_WIFI_X32_OUT") (pin "1") (pinfunction "1_1") (pintype "passive"))
      (node (ref "J_SWD") (pin "3") (pinfunction "3_3") (pintype "passive"))
      (node (ref "MCU_VCAP") (pin "1") (pinfunction "1_1") (pintype "passive"))
      (node (ref "R_MCU_BOOT0_PD") (pin "1") (pinfunction "1_1") (pintype "passive"))
      (node (ref "R_WIFI_BOOT_PD") (pin "1") (pinfunction "1_1") (pintype "passive"))
      (node (ref "R_WIFI_CS_PD") (pin "2") (pinfunction "2_2") (pintype "passive"))
      (node (ref "R_WIFI_EN_PD") (pin "2") (pinfunction "2_2") (pintype "passive"))
      (node (ref "TP_GND") (pin "TP") (pinfunction "TP_TP") (pintype "passive"))
      (node (ref "U_MCU1") (pin "10") (pinfunction "VSS_1_10") (pintype "power_in"))
      (node (ref "U_MCU1") (pin "19") (pinfunction "VSSA_19") (pintype "power_in"))
      (node (ref "U_MCU1") (pin "20") (pinfunction "VREF-_20") (pintype "power_in"))
      (node (ref "U_MCU1") (pin "27") (pinfunction "VSS_2_27") (pintype "power_in"))
      (node (ref "U_MCU1") (pin "49") (pinfunction "VSS_3_49") (pintype "power_in"))
      (node (ref "U_MCU1") (pin "74") (pinfunction "VSS_4_74") (pintype "power_in"))
      (node (ref "U_MCU1") (pin "99") (pinfunction "VSS_5_99") (pintype "power_in"))
      (node (ref "U_WIFI1") (pin "10") (pinfunction "GND_1_10") (pintype "power_in"))
      (node (ref "U_WIFI1") (pin "15") (pinfunction "GND_2_15") (pintype "power_in"))
      (node (ref "U_WIFI1") (pin "18") (pinfunction "GND_3_18") (pintype "power_in"))
      (node (ref "U_WIFI1") (pin "26") (pinfunction "GND_4_26") (pintype "power_in"))
      (node (ref "U_WIFI1") (pin "30") (pinfunction "GND_5_30") (pintype "power_in"))
      (node (ref "U_WIFI1") (pin "32") (pinfunction "GND_6_32") (pintype "power_in"))
      (node (ref "U_WIFI1") (pin "33") (pinfunction "GND_7_33") (pintype "power_in"))
      (node (ref "U_WIFI1") (pin "34") (pinfunction "GND_8_34") (pintype "power_in"))
      (node (ref "U_WIFI1") (pin "35") (pinfunction "GND_9_35") (pintype "power_in"))
      (node (ref "U_WIFI1") (pin "36") (pinfunction "GND_10_36") (pintype "power_in"))
    )
    (net (code "33") (name "I2C_SCL") (class "Default")
      (node (ref "U_MCU1") (pin "95") (pinfunction "PB8_95") (pintype "bidirectional"))
    )
    (net (code "34") (name "I2C_SDA") (class "Default")
      (node (ref "U_MCU1") (pin "96") (pinfunction "PB9_96") (pintype "bidirectional"))
    )
    (net (code "35") (name "MCU_PWR_INT_N") (class "Default")
      (node (ref "U_MCU1") (pin "83") (pinfunction "PD2_83") (pintype "bidirectional"))
    )
    (net (code "36") (name "MCU_SHUTDOWN") (class "Default")
      (node (ref "U_MCU1") (pin "86") (pinfunction "PD5_86") (pintype "bidirectional"))
    )
    (net (code "37") (name "Net-(JP_WIFI_BOOT-Pad1)") (class "Default")
      (node (ref "JP_WIFI_BOOT") (pin "1") (pinfunction "1_1") (pintype "passive"))
      (node (ref "R_WIFI_BOOT_OVR") (pin "2") (pinfunction "2_2") (pintype "passive"))
    )
    (net (code "38") (name "Net-(X_WIFI_32K-CRYSTAL_1)") (class "Default")
      (node (ref "C_WIFI_X32_IN") (pin "2") (pinfunction "2_2") (pintype "passive"))
      (node (ref "R_WIFI_X32_IN") (pin "1") (pinfunction "1_1") (pintype "passive"))
      (node (ref "X_WIFI_32K") (pin "1") (pinfunction "CRYSTAL_1_1") (pintype "passive"))
    )
    (net (code "39") (name "Net-(X_WIFI_32K-CRYSTAL_2)") (class "Default")
      (node (ref "C_WIFI_X32_OUT") (pin "2") (pinfunction "2_2") (pintype "passive"))
      (node (ref "R_WIFI_X32_OUT") (pin "1") (pinfunction "1_1") (pintype "passive"))
      (node (ref "X_WIFI_32K") (pin "2") (pinfunction "CRYSTAL_2_2") (pintype "passive"))
    )
    (net (code "40") (name "USB_PGOOD_N") (class "Default")
      (node (ref "U_MCU1") (pin "82") (pinfunction "PD1_82") (pintype "bidirectional"))
    )
    (net (code "41") (name "VOUT_1") (class "Default")
      (node (ref "R_ADC1") (pin "1") (pinfunction "1_1") (pintype "passive"))
    )
    (net (code "42") (name "VOUT_2") (class "Default")
      (node (ref "R_ADC2") (pin "1") (pinfunction "1_1") (pintype "passive"))
    )
    (net (code "43") (name "VOUT_3") (class "Default")
      (node (ref "R_ADC3") (pin "1") (pinfunction "1_1") (pintype "passive"))
    )
    (net (code "44") (name "VOUT_4") (class "Default")
      (node (ref "R_ADC4") (pin "1") (pinfunction "1_1") (pintype "passive"))
    )
    (net (code "45") (name "VOUT_5") (class "Default")
      (node (ref "R_ADC5") (pin "1") (pinfunction "1_1") (pintype "passive"))
    )
    (net (code "46") (name "unconnected-(U_MCU1-PA4-Pad29)") (class "Default")
      (node (ref "U_MCU1") (pin "29") (pinfunction "PA4_29") (pintype "bidirectional+no_connect"))
    )
    (net (code "47") (name "unconnected-(U_MCU1-PA8-Pad67)") (class "Default")
      (node (ref "U_MCU1") (pin "67") (pinfunction "PA8_67") (pintype "bidirectional+no_connect"))
    )
    (net (code "48") (name "unconnected-(U_MCU1-PA9-Pad68)") (class "Default")
      (node (ref "U_MCU1") (pin "68") (pinfunction "PA9_68") (pintype "bidirectional+no_connect"))
    )
    (net (code "49") (name "unconnected-(U_MCU1-PA10-Pad69)") (class "Default")
      (node (ref "U_MCU1") (pin "69") (pinfunction "PA10_69") (pintype "bidirectional+no_connect"))
    )
    (net (code "50") (name "unconnected-(U_MCU1-PA11-Pad70)") (class "Default")
      (node (ref "U_MCU1") (pin "70") (pinfunction "PA11_70") (pintype "bidirectional+no_connect"))
    )
    (net (code "51") (name "unconnected-(U_MCU1-PA12-Pad71)") (class "Default")
      (node (ref "U_MCU1") (pin "71") (pinfunction "PA12_71") (pintype "bidirectional+no_connect"))
    )
    (net (code "52") (name "unconnected-(U_MCU1-PA15-Pad77)") (class "Default")
      (node (ref "U_MCU1") (pin "77") (pinfunction "PA15_77") (pintype "bidirectional+no_connect"))
    )
    (net (code "53") (name "unconnected-(U_MCU1-PB1-Pad36)") (class "Default")
      (node (ref "U_MCU1") (pin "36") (pinfunction "PB1_36") (pintype "bidirectional+no_connect"))
    )
    (net (code "54") (name "unconnected-(U_MCU1-PB2-Pad37)") (class "Default")
      (node (ref "U_MCU1") (pin "37") (pinfunction "PB2_37") (pintype "bidirectional+no_connect"))
    )
    (net (code "55") (name "unconnected-(U_MCU1-PB4-Pad90)") (class "Default")
      (node (ref "U_MCU1") (pin "90") (pinfunction "PB4_90") (pintype "bidirectional+no_connect"))
    )
    (net (code "56") (name "unconnected-(U_MCU1-PB10-Pad47)") (class "Default")
      (node (ref "U_MCU1") (pin "47") (pinfunction "PB10_47") (pintype "bidirectional+no_connect"))
    )
    (net (code "57") (name "unconnected-(U_MCU1-PB12-Pad51)") (class "Default")
      (node (ref "U_MCU1") (pin "51") (pinfunction "PB12_51") (pintype "bidirectional+no_connect"))
    )
    (net (code "58") (name "unconnected-(U_MCU1-PB13-Pad52)") (class "Default")
      (node (ref "U_MCU1") (pin "52") (pinfunction "PB13_52") (pintype "bidirectional+no_connect"))
    )
    (net (code "59") (name "unconnected-(U_MCU1-PB14-Pad53)") (class "Default")
      (node (ref "U_MCU1") (pin "53") (pinfunction "PB14_53") (pintype "bidirectional+no_connect"))
    )
    (net (code "60") (name "unconnected-(U_MCU1-PB15-Pad54)") (class "Default")
      (node (ref "U_MCU1") (pin "54") (pinfunction "PB15_54") (pintype "bidirectional+no_connect"))
    )
    (net (code "61") (name "unconnected-(U_MCU1-PC0-Pad15)") (class "Default")
      (node (ref "U_MCU1") (pin "15") (pinfunction "PC0_15") (pintype "bidirectional+no_connect"))
    )
    (net (code "62") (name "unconnected-(U_MCU1-PC1-Pad16)") (class "Default")
      (node (ref "U_MCU1") (pin "16") (pinfunction "PC1_16") (pintype "bidirectional+no_connect"))
    )
    (net (code "63") (name "unconnected-(U_MCU1-PC2-Pad17)") (class "Default")
      (node (ref "U_MCU1") (pin "17") (pinfunction "PC2_17") (pintype "bidirectional+no_connect"))
    )
    (net (code "64") (name "unconnected-(U_MCU1-PC3-Pad18)") (class "Default")
      (node (ref "U_MCU1") (pin "18") (pinfunction "PC3_18") (pintype "bidirectional+no_connect"))
    )
    (net (code "65") (name "unconnected-(U_MCU1-PC5-Pad34)") (class "Default")
      (node (ref "U_MCU1") (pin "34") (pinfunction "PC5_34") (pintype "bidirectional+no_connect"))
    )
    (net (code "66") (name "unconnected-(U_MCU1-PC6-Pad63)") (class "Default")
      (node (ref "U_MCU1") (pin "63") (pinfunction "PC6_63") (pintype "bidirectional+no_connect"))
    )
    (net (code "67") (name "unconnected-(U_MCU1-PC7-Pad64)") (class "Default")
      (node (ref "U_MCU1") (pin "64") (pinfunction "PC7_64") (pintype "bidirectional+no_connect"))
    )
    (net (code "68") (name "unconnected-(U_MCU1-PC8-Pad65)") (class "Default")
      (node (ref "U_MCU1") (pin "65") (pinfunction "PC8_65") (pintype "bidirectional+no_connect"))
    )
    (net (code "69") (name "unconnected-(U_MCU1-PC9-Pad66)") (class "Default")
      (node (ref "U_MCU1") (pin "66") (pinfunction "PC9_66") (pintype "bidirectional+no_connect"))
    )
    (net (code "70") (name "unconnected-(U_MCU1-PC10-Pad78)") (class "Default")
      (node (ref "U_MCU1") (pin "78") (pinfunction "PC10_78") (pintype "bidirectional+no_connect"))
    )
    (net (code "71") (name "unconnected-(U_MCU1-PC11-Pad79)") (class "Default")
      (node (ref "U_MCU1") (pin "79") (pinfunction "PC11_79") (pintype "bidirectional+no_connect"))
    )
    (net (code "72") (name "unconnected-(U_MCU1-PC12-Pad80)") (class "Default")
      (node (ref "U_MCU1") (pin "80") (pinfunction "PC12_80") (pintype "bidirectional+no_connect"))
    )
    (net (code "73") (name "unconnected-(U_MCU1-PC13-Pad7)") (class "Default")
      (node (ref "U_MCU1") (pin "7") (pinfunction "PC13_7") (pintype "bidirectional+no_connect"))
    )
    (net (code "74") (name "unconnected-(U_MCU1-PC14-OSC32_IN-Pad8)") (class "Default")
      (node (ref "U_MCU1") (pin "8") (pinfunction "PC14-OSC32_IN_8") (pintype "bidirectional+no_connect"))
    )
    (net (code "75") (name "unconnected-(U_MCU1-PC15-OSC32_OUT-Pad9)") (class "Default")
      (node (ref "U_MCU1") (pin "9") (pinfunction "PC15-OSC32_OUT_9") (pintype "bidirectional+no_connect"))
    )
    (net (code "76") (name "unconnected-(U_MCU1-PD3-Pad84)") (class "Default")
      (node (ref "U_MCU1") (pin "84") (pinfunction "PD3_84") (pintype "bidirectional+no_connect"))
    )
    (net (code "77") (name "unconnected-(U_MCU1-PD7-Pad88)") (class "Default")
      (node (ref "U_MCU1") (pin "88") (pinfunction "PD7_88") (pintype "bidirectional+no_connect"))
    )
    (net (code "78") (name "unconnected-(U_MCU1-PD8-Pad55)") (class "Default")
      (node (ref "U_MCU1") (pin "55") (pinfunction "PD8_55") (pintype "bidirectional+no_connect"))
    )
    (net (code "79") (name "unconnected-(U_MCU1-PD9-Pad56)") (class "Default")
      (node (ref "U_MCU1") (pin "56") (pinfunction "PD9_56") (pintype "bidirectional+no_connect"))
    )
    (net (code "80") (name "unconnected-(U_MCU1-PD10-Pad57)") (class "Default")
      (node (ref "U_MCU1") (pin "57") (pinfunction "PD10_57") (pintype "bidirectional+no_connect"))
    )
    (net (code "81") (name "unconnected-(U_MCU1-PD11-Pad58)") (class "Default")
      (node (ref "U_MCU1") (pin "58") (pinfunction "PD11_58") (pintype "bidirectional+no_connect"))
    )
    (net (code "82") (name "unconnected-(U_MCU1-PD12-Pad59)") (class "Default")
      (node (ref "U_MCU1") (pin "59") (pinfunction "PD12_59") (pintype "bidirectional+no_connect"))
    )
    (net (code "83") (name "unconnected-(U_MCU1-PD13-Pad60)") (class "Default")
      (node (ref "U_MCU1") (pin "60") (pinfunction "PD13_60") (pintype "bidirectional+no_connect"))
    )
    (net (code "84") (name "unconnected-(U_MCU1-PD14-Pad61)") (class "Default")
      (node (ref "U_MCU1") (pin "61") (pinfunction "PD14_61") (pintype "bidirectional+no_connect"))
    )
    (net (code "85") (name "unconnected-(U_MCU1-PD15-Pad62)") (class "Default")
      (node (ref "U_MCU1") (pin "62") (pinfunction "PD15_62") (pintype "bidirectional+no_connect"))
    )
    (net (code "86") (name "unconnected-(U_MCU1-PE0-Pad97)") (class "Default")
      (node (ref "U_MCU1") (pin "97") (pinfunction "PE0_97") (pintype "bidirectional+no_connect"))
    )
    (net (code "87") (name "unconnected-(U_MCU1-PE1-Pad98)") (class "Default")
      (node (ref "U_MCU1") (pin "98") (pinfunction "PE1_98") (pintype "bidirectional+no_connect"))
    )
    (net (code "88") (name "unconnected-(U_MCU1-PE2-Pad1)") (class "Default")
      (node (ref "U_MCU1") (pin "1") (pinfunction "PE2_1") (pintype "bidirectional+no_connect"))
    )
    (net (code "89") (name "unconnected-(U_MCU1-PE3-Pad2)") (class "Default")
      (node (ref "U_MCU1") (pin "2") (pinfunction "PE3_2") (pintype "bidirectional+no_connect"))
    )
    (net (code "90") (name "unconnected-(U_MCU1-PE4-Pad3)") (class "Default")
      (node (ref "U_MCU1") (pin "3") (pinfunction "PE4_3") (pintype "bidirectional+no_connect"))
    )
    (net (code "91") (name "unconnected-(U_MCU1-PE5-Pad4)") (class "Default")
      (node (ref "U_MCU1") (pin "4") (pinfunction "PE5_4") (pintype "bidirectional+no_connect"))
    )
    (net (code "92") (name "unconnected-(U_MCU1-PE6-Pad5)") (class "Default")
      (node (ref "U_MCU1") (pin "5") (pinfunction "PE6_5") (pintype "bidirectional+no_connect"))
    )
    (net (code "93") (name "unconnected-(U_MCU1-PE7-Pad38)") (class "Default")
      (node (ref "U_MCU1") (pin "38") (pinfunction "PE7_38") (pintype "bidirectional+no_connect"))
    )
    (net (code "94") (name "unconnected-(U_MCU1-PE8-Pad39)") (class "Default")
      (node (ref "U_MCU1") (pin "39") (pinfunction "PE8_39") (pintype "bidirectional+no_connect"))
    )
    (net (code "95") (name "unconnected-(U_MCU1-PE9-Pad40)") (class "Default")
      (node (ref "U_MCU1") (pin "40") (pinfunction "PE9_40") (pintype "bidirectional+no_connect"))
    )
    (net (code "96") (name "unconnected-(U_MCU1-PE10-Pad41)") (class "Default")
      (node (ref "U_MCU1") (pin "41") (pinfunction "PE10_41") (pintype "bidirectional+no_connect"))
    )
    (net (code "97") (name "unconnected-(U_MCU1-PE11-Pad42)") (class "Default")
      (node (ref "U_MCU1") (pin "42") (pinfunction "PE11_42") (pintype "bidirectional+no_connect"))
    )
    (net (code "98") (name "unconnected-(U_MCU1-PE12-Pad43)") (class "Default")
      (node (ref "U_MCU1") (pin "43") (pinfunction "PE12_43") (pintype "bidirectional+no_connect"))
    )
    (net (code "99") (name "unconnected-(U_MCU1-PE13-Pad44)") (class "Default")
      (node (ref "U_MCU1") (pin "44") (pinfunction "PE13_44") (pintype "bidirectional+no_connect"))
    )
    (net (code "100") (name "unconnected-(U_MCU1-PE14-Pad45)") (class "Default")
      (node (ref "U_MCU1") (pin "45") (pinfunction "PE14_45") (pintype "bidirectional+no_connect"))
    )
    (net (code "101") (name "unconnected-(U_MCU1-PE15-Pad46)") (class "Default")
      (node (ref "U_MCU1") (pin "46") (pinfunction "PE15_46") (pintype "bidirectional+no_connect"))
    )
    (net (code "102") (name "unconnected-(U_MCU1-PH0-OSC_IN-Pad12)") (class "Default")
      (node (ref "U_MCU1") (pin "12") (pinfunction "PH0-OSC_IN_12") (pintype "bidirectional+no_connect"))
    )
    (net (code "103") (name "unconnected-(U_MCU1-PH1-OSC_OUT-Pad13)") (class "Default")
      (node (ref "U_MCU1") (pin "13") (pinfunction "PH1-OSC_OUT_13") (pintype "bidirectional+no_connect"))
    )
    (net (code "104") (name "unconnected-(U_WIFI1-NC_3-Pad31)") (class "Default")
      (node (ref "U_WIFI1") (pin "31") (pinfunction "NC_3_31") (pintype "passive"))
    )
    (net (code "105") (name "unconnected-(U_WIFI1-RESERVED-Pad19)") (class "Default")
      (node (ref "U_WIFI1") (pin "19") (pinfunction "RESERVED_19") (pintype "passive"))
    )
    (net (code "106") (name "unconnected-(U_WIFI1-RESERVED-Pad20)") (class "Default")
      (node (ref "U_WIFI1") (pin "20") (pinfunction "RESERVED_20") (pintype "passive"))
    )
    (net (code "107") (name "unconnected-(U_WIFI1-RESERVED_1-Pad1)") (class "Default")
      (node (ref "U_WIFI1") (pin "1") (pinfunction "RESERVED_1_1") (pintype "passive"))
    )
    (net (code "108") (name "unconnected-(U_WIFI1-RESERVED_2-Pad2)") (class "Default")
      (node (ref "U_WIFI1") (pin "2") (pinfunction "RESERVED_2_2") (pintype "passive"))
    )
    (net (code "109") (name "unconnected-(U_WIFI1-RESERVED_3-Pad4)") (class "Default")
      (node (ref "U_WIFI1") (pin "4") (pinfunction "RESERVED_3_4") (pintype "passive+no_connect"))
    )
    (net (code "110") (name "unconnected-(U_WIFI1-RESERVED_4-Pad5)") (class "Default")
      (node (ref "U_WIFI1") (pin "5") (pinfunction "RESERVED_4_5") (pintype "passive+no_connect"))
    )
    (net (code "111") (name "unconnected-(U_WIFI1-RESERVED_5-Pad6)") (class "Default")
      (node (ref "U_WIFI1") (pin "6") (pinfunction "RESERVED_5_6") (pintype "passive+no_connect"))
    )
    (net (code "112") (name "unconnected-(U_WIFI1-RESERVED_6-Pad7)") (class "Default")
      (node (ref "U_WIFI1") (pin "7") (pinfunction "RESERVED_6_7") (pintype "passive+no_connect"))
    )
    (net (code "113") (name "unconnected-(U_WIFI1-RESERVED_7-Pad8)") (class "Default")
      (node (ref "U_WIFI1") (pin "8") (pinfunction "RESERVED_7_8") (pintype "passive+no_connect"))
    )
    (net (code "114") (name "unconnected-(U_WIFI1-RESERVED_8-Pad11)") (class "Default")
      (node (ref "U_WIFI1") (pin "11") (pinfunction "RESERVED_8_11") (pintype "passive+no_connect"))
    )
    (net (code "115") (name "unconnected-(U_WIFI1-RESERVED_9-Pad12)") (class "Default")
      (node (ref "U_WIFI1") (pin "12") (pinfunction "RESERVED_9_12") (pintype "passive+no_connect"))
    )
  )
)
